# Power.net
KiCad netlist of a schematic drawn in Altium Designer
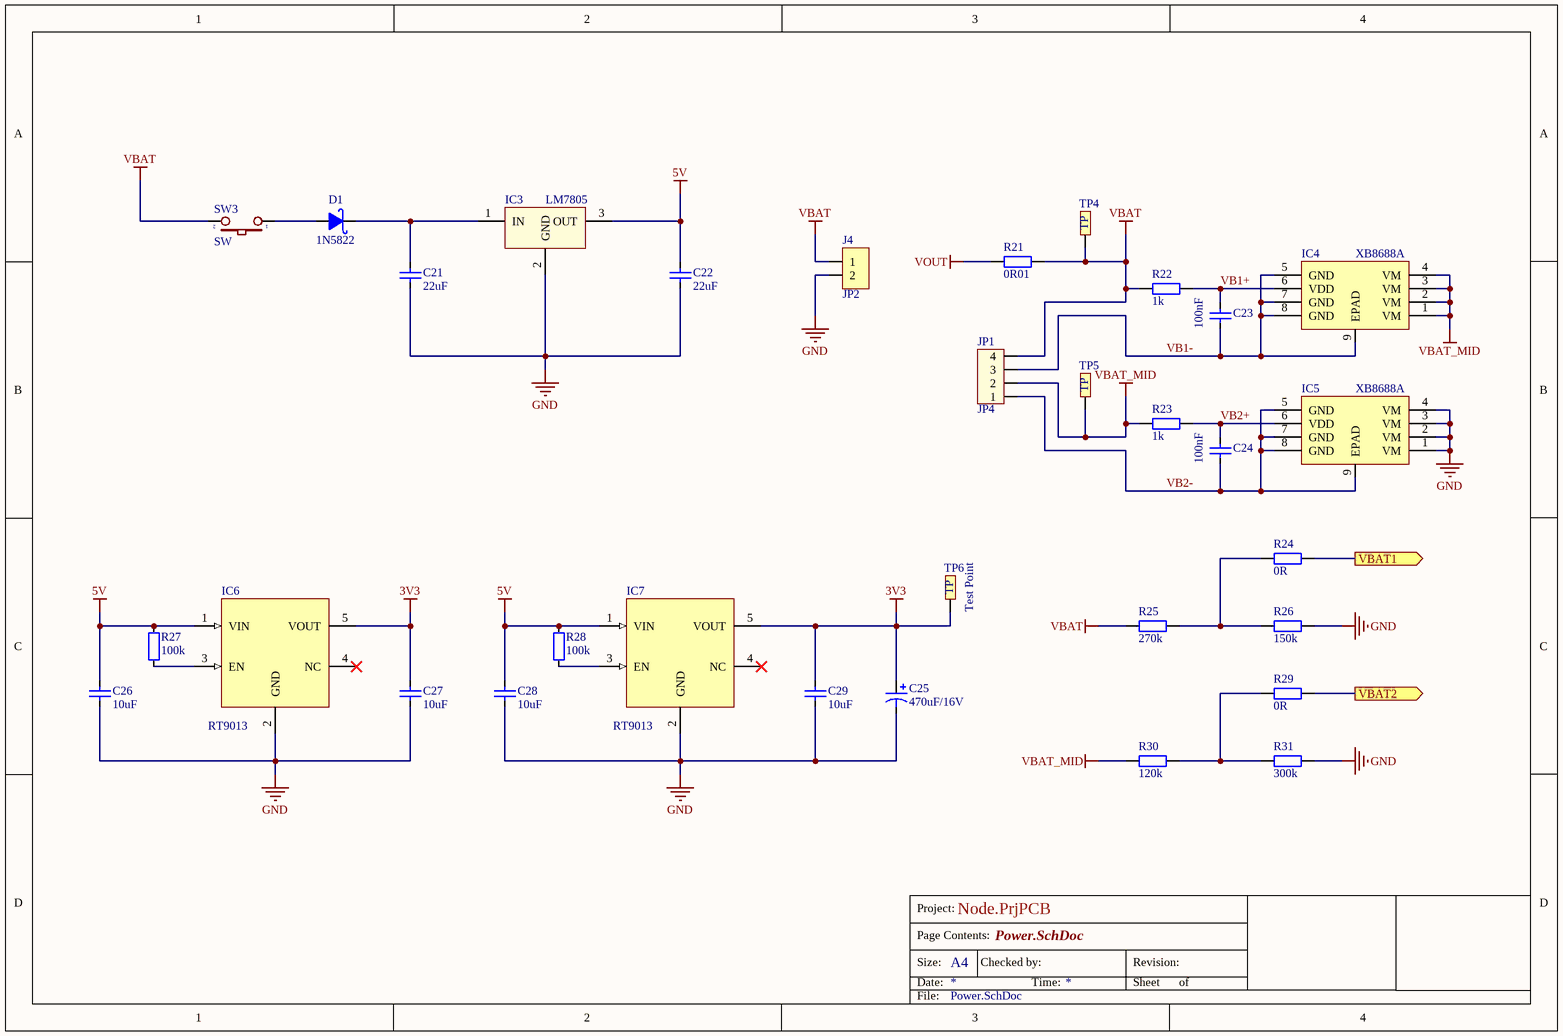
[diagram p0: Power.SchDoc]

(export (version "E")
  (design (tool "Eeschema 10.0.6"))
  (components
    (comp (ref "C21")
      (value "22uF")
      (footprint "CAP_0805")
      (description "Capacitor")
      (fields (field (name "PUBLISHER") "Altium Limited"))
      (libsource (lib "My Library") (part "CapSMD"))
    )
    (comp (ref "C22")
      (value "22uF")
      (footprint "CAP_0805")
      (description "Capacitor")
      (fields (field (name "PUBLISHER") "Altium Limited"))
      (libsource (lib "My Library") (part "CapSMD"))
    )
    (comp (ref "C23")
      (value "100nF")
      (footprint "CAP_0805")
      (description "Capacitor")
      (fields (field (name "PUBLISHER") "Altium Limited"))
      (libsource (lib "My Library") (part "CapSMD"))
    )
    (comp (ref "C24")
      (value "100nF")
      (footprint "CAP_0805")
      (description "Capacitor")
      (fields (field (name "PUBLISHER") "Altium Limited"))
      (libsource (lib "My Library") (part "CapSMD"))
    )
    (comp (ref "C25")
      (value "470uF/16V")
      (footprint "C8mm")
      (description "Polarized Capacitor (Axial)")
      (fields (field (name "PUBLISHER") "Altium Limited"))
      (libsource (lib "My Library") (part "Cap Pol"))
    )
    (comp (ref "C26")
      (value "10uF")
      (footprint "CAP_0805")
      (description "Capacitor")
      (fields (field (name "PUBLISHER") "Altium Limited"))
      (libsource (lib "My Library") (part "CapSMD"))
    )
    (comp (ref "C27")
      (value "10uF")
      (footprint "CAP_0805")
      (description "Capacitor")
      (fields (field (name "PUBLISHER") "Altium Limited"))
      (libsource (lib "My Library") (part "CapSMD"))
    )
    (comp (ref "C28")
      (value "10uF")
      (footprint "CAP_0805")
      (description "Capacitor")
      (fields (field (name "PUBLISHER") "Altium Limited"))
      (libsource (lib "My Library") (part "CapSMD"))
    )
    (comp (ref "C29")
      (value "10uF")
      (footprint "CAP_0805")
      (description "Capacitor")
      (fields (field (name "PUBLISHER") "Altium Limited"))
      (libsource (lib "My Library") (part "CapSMD"))
    )
    (comp (ref "D1")
      (value "1N5822")
      (footprint "DIO-214AC(SMA)")
      (description "Schottky Rectifiers")
      (libsource (lib "My Library") (part "1N5822"))
    )
    (comp (ref "IC3")
      (value "LM7805")
      (footprint "TO-252")
      (description "LDO to 5V")
      (libsource (lib "My Library") (part "LM78xx"))
    )
    (comp (ref "IC4")
      (value "XB8688A")
      (footprint "SOP8-PP")
      (description "One Cell Lithium-ion/Polymer Battery Protection IC")
      (libsource (lib "My Library") (part "XB8688"))
    )
    (comp (ref "IC5")
      (value "XB8688A")
      (footprint "SOP8-PP")
      (description "One Cell Lithium-ion/Polymer Battery Protection IC")
      (libsource (lib "My Library") (part "XB8688"))
    )
    (comp (ref "IC6")
      (value "RT9013")
      (footprint "SOT23-5")
      (description "RT9013-33GB IC REG LINEAR 3.3V 500mA SOT23-5")
      (libsource (lib "My Library") (part "RT9013"))
    )
    (comp (ref "IC7")
      (value "RT9013")
      (footprint "SOT23-5")
      (description "RT9013-33GB IC REG LINEAR 3.3V 500mA SOT23-5")
      (libsource (lib "My Library") (part "RT9013"))
    )
    (comp (ref "J4")
      (value "JP2")
      (footprint "JP2-D1T")
      (description "WR-PHD 2.54 mm Angled Socket Header")
      (fields
        (field (name "MANUFACTURER") "Würth Elektronik eiSos GmbH")
        (field (name "PARTNO") "613002143121")
        (field (name "CREATED BY") "Karrer Zheng")
      )
      (libsource (lib "My Library") (part "JP2"))
    )
    (comp (ref "JP1")
      (value "JP4")
      (footprint "CON4")
      (description "Connector 4")
      (libsource (lib "My Library") (part "Con4"))
    )
    (comp (ref "R21")
      (value "0R01")
      (footprint "RES-SMD-2512")
      (description "Resistor SMD")
      (fields
        (field (name "MANUFACTURER") "Generic Components")
        (field (name "PUBLISHER") "Altium Hobart Technology Centre")
      )
      (libsource (lib "My Library") (part "Resistor - SMD"))
    )
    (comp (ref "R22")
      (value "1k")
      (footprint "RES-SMD-0805")
      (description "Resistor SMD")
      (fields
        (field (name "MANUFACTURER") "Generic Components")
        (field (name "PUBLISHER") "Altium Hobart Technology Centre")
      )
      (libsource (lib "My Library") (part "Resistor - SMD"))
    )
    (comp (ref "R23")
      (value "1k")
      (footprint "RES-SMD-0805")
      (description "Resistor SMD")
      (fields
        (field (name "MANUFACTURER") "Generic Components")
        (field (name "PUBLISHER") "Altium Hobart Technology Centre")
      )
      (libsource (lib "My Library") (part "Resistor - SMD"))
    )
    (comp (ref "R24")
      (value "0R")
      (footprint "RES-SMD-0805")
      (description "Resistor SMD")
      (fields
        (field (name "MANUFACTURER") "Generic Components")
        (field (name "PUBLISHER") "Altium Hobart Technology Centre")
      )
      (libsource (lib "My Library") (part "Resistor - SMD"))
    )
    (comp (ref "R25")
      (value "270k")
      (footprint "RES-SMD-0805")
      (description "Resistor SMD")
      (fields
        (field (name "MANUFACTURER") "Generic Components")
        (field (name "PUBLISHER") "Altium Hobart Technology Centre")
      )
      (libsource (lib "My Library") (part "Resistor - SMD"))
    )
    (comp (ref "R26")
      (value "150k")
      (footprint "RES-SMD-0805")
      (description "Resistor SMD")
      (fields
        (field (name "MANUFACTURER") "Generic Components")
        (field (name "PUBLISHER") "Altium Hobart Technology Centre")
      )
      (libsource (lib "My Library") (part "Resistor - SMD"))
    )
    (comp (ref "R27")
      (value "100k")
      (footprint "RES-SMD-0805")
      (description "Resistor")
      (fields
        (field (name "MANUFACTURER") "Generic Components")
        (field (name "PUBLISHER") "Altium Hobart Technology Centre")
      )
      (libsource (lib "") (part "Resistor - SMD_1"))
    )
    (comp (ref "R28")
      (value "100k")
      (footprint "RES-SMD-0805")
      (description "Resistor")
      (fields
        (field (name "MANUFACTURER") "Generic Components")
        (field (name "PUBLISHER") "Altium Hobart Technology Centre")
      )
      (libsource (lib "") (part "Resistor - SMD_1"))
    )
    (comp (ref "R29")
      (value "0R")
      (footprint "RES-SMD-0805")
      (description "Resistor SMD")
      (fields
        (field (name "MANUFACTURER") "Generic Components")
        (field (name "PUBLISHER") "Altium Hobart Technology Centre")
      )
      (libsource (lib "My Library") (part "Resistor - SMD"))
    )
    (comp (ref "R30")
      (value "120k")
      (footprint "RES-SMD-0805")
      (description "Resistor SMD")
      (fields
        (field (name "MANUFACTURER") "Generic Components")
        (field (name "PUBLISHER") "Altium Hobart Technology Centre")
      )
      (libsource (lib "My Library") (part "Resistor - SMD"))
    )
    (comp (ref "R31")
      (value "300k")
      (footprint "RES-SMD-0805")
      (description "Resistor SMD")
      (fields
        (field (name "MANUFACTURER") "Generic Components")
        (field (name "PUBLISHER") "Altium Hobart Technology Centre")
      )
      (libsource (lib "My Library") (part "Resistor - SMD"))
    )
    (comp (ref "SW3")
      (value "SW")
      (footprint "SW102")
      (description "Switch button 2 pin")
      (libsource (lib "My Library") (part "SW2"))
    )
    (comp (ref "TP4")
      (value "Test Point")
      (footprint "TP_SMD")
      (description "CONNECT 1")
      (libsource (lib "My Library") (part "TP"))
    )
    (comp (ref "TP5")
      (value "Test Point")
      (footprint "TP_SMD")
      (description "CONNECT 1")
      (libsource (lib "My Library") (part "TP"))
    )
    (comp (ref "TP6")
      (value "Test Point")
      (footprint "TP_SMD")
      (description "CONNECT 1")
      (libsource (lib "My Library") (part "TP"))
    )
  )
  (nets
    (net (code "1") (name "/VB1+") (class "Default")
      (node (ref "C23") (pin "2") (pinfunction "2_2") (pintype "passive"))
      (node (ref "IC4") (pin "6") (pinfunction "VDD_6") (pintype "passive"))
      (node (ref "R22") (pin "1") (pinfunction "1_1") (pintype "passive"))
    )
    (net (code "2") (name "/VB1-") (class "Default")
      (node (ref "C23") (pin "1") (pinfunction "1_1") (pintype "passive"))
      (node (ref "IC4") (pin "5") (pinfunction "GND_5") (pintype "passive"))
      (node (ref "IC4") (pin "7") (pinfunction "GND_7") (pintype "passive"))
      (node (ref "IC4") (pin "8") (pinfunction "GND_8") (pintype "passive"))
      (node (ref "IC4") (pin "9") (pinfunction "EPAD_9") (pintype "passive"))
      (node (ref "JP1") (pin "3") (pinfunction "3_3") (pintype "passive"))
    )
    (net (code "3") (name "/VB2+") (class "Default")
      (node (ref "C24") (pin "2") (pinfunction "2_2") (pintype "passive"))
      (node (ref "IC5") (pin "6") (pinfunction "VDD_6") (pintype "passive"))
      (node (ref "R23") (pin "1") (pinfunction "1_1") (pintype "passive"))
    )
    (net (code "4") (name "/VB2-") (class "Default")
      (node (ref "C24") (pin "1") (pinfunction "1_1") (pintype "passive"))
      (node (ref "IC5") (pin "5") (pinfunction "GND_5") (pintype "passive"))
      (node (ref "IC5") (pin "7") (pinfunction "GND_7") (pintype "passive"))
      (node (ref "IC5") (pin "8") (pinfunction "GND_8") (pintype "passive"))
      (node (ref "IC5") (pin "9") (pinfunction "EPAD_9") (pintype "passive"))
      (node (ref "JP1") (pin "1") (pinfunction "1_1") (pintype "passive"))
    )
    (net (code "5") (name "/VBAT1") (class "Default")
      (node (ref "R24") (pin "1") (pinfunction "1_1") (pintype "passive"))
    )
    (net (code "6") (name "/VBAT2") (class "Default")
      (node (ref "R29") (pin "1") (pinfunction "1_1") (pintype "passive"))
    )
    (net (code "7") (name "3V3") (class "Default")
      (node (ref "C25") (pin "1") (pinfunction "1_1") (pintype "passive"))
      (node (ref "C27") (pin "2") (pinfunction "2_2") (pintype "passive"))
      (node (ref "C29") (pin "2") (pinfunction "2_2") (pintype "passive"))
      (node (ref "IC6") (pin "5") (pinfunction "VOUT_5") (pintype "power_in"))
      (node (ref "IC7") (pin "5") (pinfunction "VOUT_5") (pintype "power_in"))
      (node (ref "TP6") (pin "1") (pinfunction "0_1") (pintype "passive"))
    )
    (net (code "8") (name "5V") (class "Default")
      (node (ref "C22") (pin "2") (pinfunction "2_2") (pintype "passive"))
      (node (ref "C26") (pin "2") (pinfunction "2_2") (pintype "passive"))
      (node (ref "C28") (pin "2") (pinfunction "2_2") (pintype "passive"))
      (node (ref "IC3") (pin "3") (pinfunction "OUT_3") (pintype "passive"))
      (node (ref "IC6") (pin "1") (pinfunction "VIN_1") (pintype "input"))
      (node (ref "IC7") (pin "1") (pinfunction "VIN_1") (pintype "input"))
      (node (ref "R27") (pin "1") (pinfunction "1_1") (pintype "passive"))
      (node (ref "R28") (pin "1") (pinfunction "1_1") (pintype "passive"))
    )
    (net (code "9") (name "GND") (class "Default")
      (node (ref "C21") (pin "1") (pinfunction "1_1") (pintype "passive"))
      (node (ref "C22") (pin "1") (pinfunction "1_1") (pintype "passive"))
      (node (ref "C25") (pin "2") (pinfunction "2_2") (pintype "passive"))
      (node (ref "C26") (pin "1") (pinfunction "1_1") (pintype "passive"))
      (node (ref "C27") (pin "1") (pinfunction "1_1") (pintype "passive"))
      (node (ref "C28") (pin "1") (pinfunction "1_1") (pintype "passive"))
      (node (ref "C29") (pin "1") (pinfunction "1_1") (pintype "passive"))
      (node (ref "IC3") (pin "2") (pinfunction "GND_2") (pintype "passive"))
      (node (ref "IC5") (pin "1") (pinfunction "VM_1") (pintype "passive"))
      (node (ref "IC5") (pin "2") (pinfunction "VM_2") (pintype "passive"))
      (node (ref "IC5") (pin "3") (pinfunction "VM_3") (pintype "passive"))
      (node (ref "IC5") (pin "4") (pinfunction "VM_4") (pintype "passive"))
      (node (ref "IC6") (pin "2") (pinfunction "GND_2") (pintype "passive"))
      (node (ref "IC7") (pin "2") (pinfunction "GND_2") (pintype "passive"))
      (node (ref "J4") (pin "2") (pinfunction "2_2") (pintype "passive"))
      (node (ref "R26") (pin "1") (pinfunction "1_1") (pintype "passive"))
      (node (ref "R31") (pin "1") (pinfunction "1_1") (pintype "passive"))
    )
    (net (code "10") (name "Net-(D1-A)") (class "Default")
      (node (ref "D1") (pin "1") (pinfunction "A_1") (pintype "passive"))
      (node (ref "SW3") (pin "1") (pinfunction "1_1") (pintype "passive"))
    )
    (net (code "11") (name "Net-(D1-K)") (class "Default")
      (node (ref "C21") (pin "2") (pinfunction "2_2") (pintype "passive"))
      (node (ref "D1") (pin "2") (pinfunction "K_2") (pintype "passive"))
      (node (ref "IC3") (pin "1") (pinfunction "IN_1") (pintype "passive"))
    )
    (net (code "12") (name "Net-(IC6-EN)") (class "Default")
      (node (ref "IC6") (pin "3") (pinfunction "EN_3") (pintype "input"))
      (node (ref "R27") (pin "2") (pinfunction "2_2") (pintype "passive"))
    )
    (net (code "13") (name "Net-(IC7-EN)") (class "Default")
      (node (ref "IC7") (pin "3") (pinfunction "EN_3") (pintype "input"))
      (node (ref "R28") (pin "2") (pinfunction "2_2") (pintype "passive"))
    )
    (net (code "14") (name "Net-(R24-Pad2)") (class "Default")
      (node (ref "R24") (pin "2") (pinfunction "2_2") (pintype "passive"))
      (node (ref "R25") (pin "1") (pinfunction "1_1") (pintype "passive"))
      (node (ref "R26") (pin "2") (pinfunction "2_2") (pintype "passive"))
    )
    (net (code "15") (name "Net-(R29-Pad2)") (class "Default")
      (node (ref "R29") (pin "2") (pinfunction "2_2") (pintype "passive"))
      (node (ref "R30") (pin "1") (pinfunction "1_1") (pintype "passive"))
      (node (ref "R31") (pin "2") (pinfunction "2_2") (pintype "passive"))
    )
    (net (code "16") (name "VBAT") (class "Default")
      (node (ref "J4") (pin "1") (pinfunction "1_1") (pintype "passive"))
      (node (ref "JP1") (pin "4") (pinfunction "4_4") (pintype "passive"))
      (node (ref "R21") (pin "2") (pinfunction "2_2") (pintype "passive"))
      (node (ref "R22") (pin "2") (pinfunction "2_2") (pintype "passive"))
      (node (ref "R25") (pin "2") (pinfunction "2_2") (pintype "passive"))
      (node (ref "SW3") (pin "2") (pinfunction "2_2") (pintype "passive"))
      (node (ref "TP4") (pin "1") (pinfunction "0_1") (pintype "passive"))
    )
    (net (code "17") (name "VBAT_MID") (class "Default")
      (node (ref "IC4") (pin "1") (pinfunction "VM_1") (pintype "passive"))
      (node (ref "IC4") (pin "2") (pinfunction "VM_2") (pintype "passive"))
      (node (ref "IC4") (pin "3") (pinfunction "VM_3") (pintype "passive"))
      (node (ref "IC4") (pin "4") (pinfunction "VM_4") (pintype "passive"))
      (node (ref "JP1") (pin "2") (pinfunction "2_2") (pintype "passive"))
      (node (ref "R23") (pin "2") (pinfunction "2_2") (pintype "passive"))
      (node (ref "R30") (pin "2") (pinfunction "2_2") (pintype "passive"))
      (node (ref "TP5") (pin "1") (pinfunction "0_1") (pintype "passive"))
    )
    (net (code "18") (name "VOUT") (class "Default")
      (node (ref "R21") (pin "1") (pinfunction "1_1") (pintype "passive"))
    )
    (net (code "19") (name "unconnected-(IC6-NC-Pad4)") (class "Default")
      (node (ref "IC6") (pin "4") (pinfunction "NC_4") (pintype "passive+no_connect"))
    )
    (net (code "20") (name "unconnected-(IC7-NC-Pad4)") (class "Default")
      (node (ref "IC7") (pin "4") (pinfunction "NC_4") (pintype "passive+no_connect"))
    )
  )
)
